# GC-Sch2.net
KiCad netlist of a schematic drawn in Altium Designer
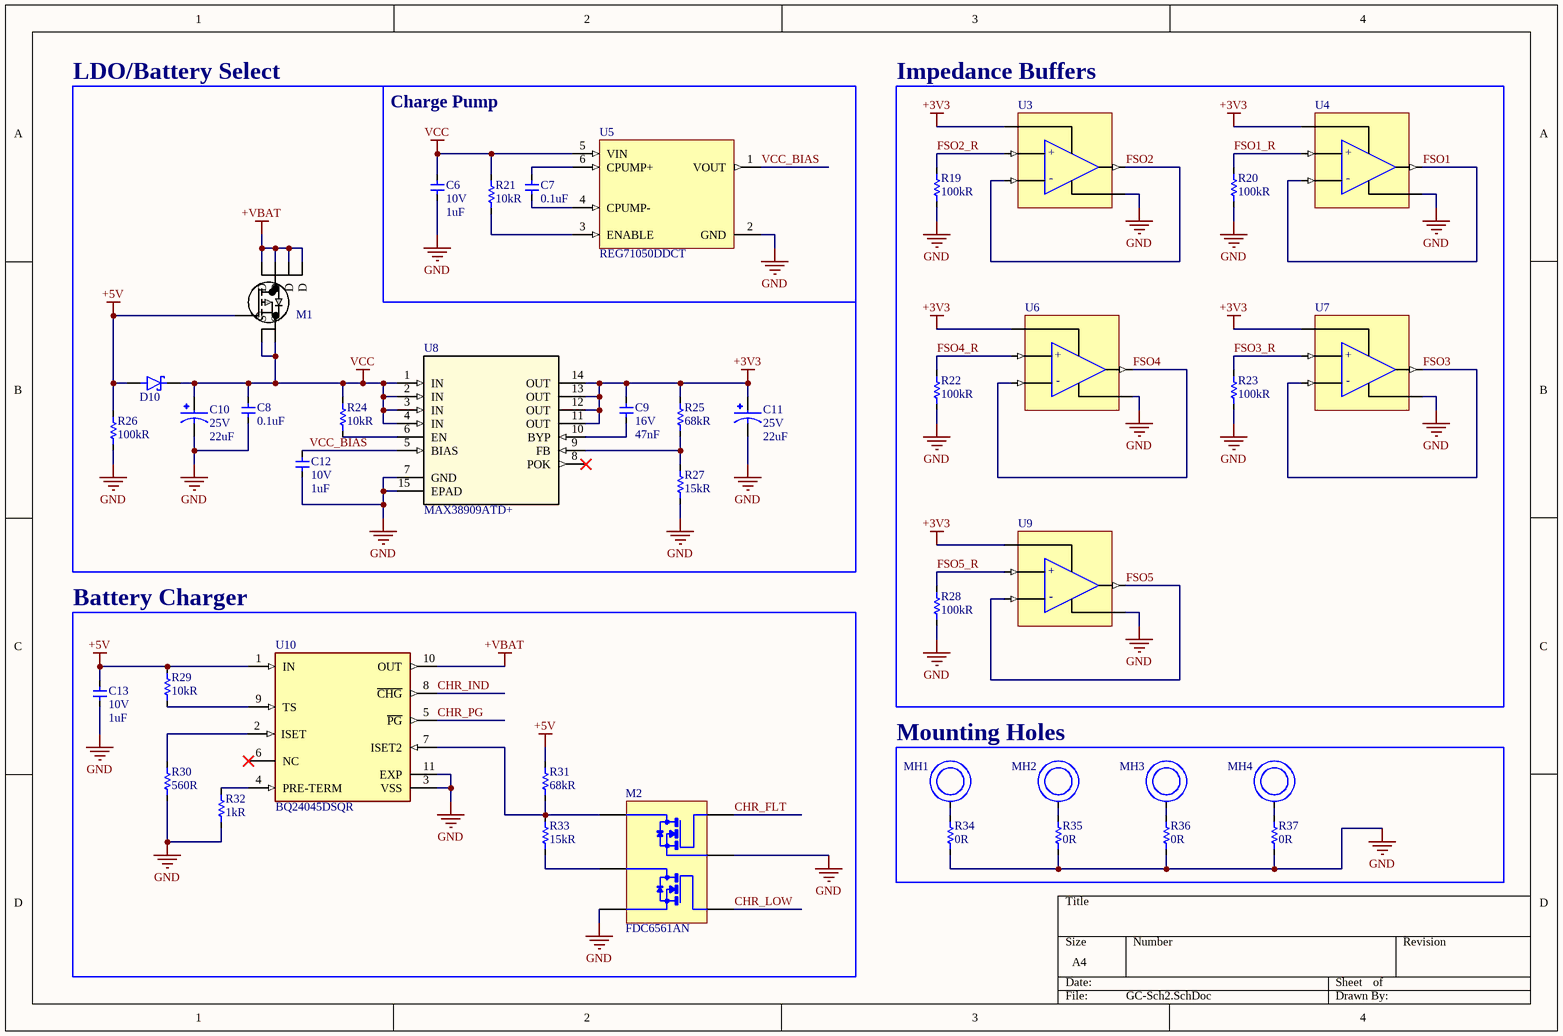
[diagram p0: GC-Sch2.SchDoc]

(export (version "E")
  (design (tool "Eeschema 10.0.6"))
  (components
    (comp (ref "C6")
      (value "CL10B105KP8NNNC")
      (footprint "0603 - C")
      (fields
        (field (name "MANUFACTURER") "Samsung")
        (field (name "RATED DC VOLTAGE (URDC)") "10V")
        (field (name "CAPACITANCE") "1uF")
      )
      (libsource (lib "GC-Schlib1") (part "CC-CL10B105KP8NNNC"))
    )
    (comp (ref "C7")
      (value "CL10B104JB8NNNC")
      (footprint "0603 - C")
      (fields (field (name "MANUFACTURER") "Samsung") (field (name "CAPACITANCE") "0.1uF"))
      (libsource (lib "GC-Schlib1") (part "CC-CL10B104JB8NNNC"))
    )
    (comp (ref "C8")
      (value "CL10B104JB8NNNC")
      (footprint "0603")
      (fields (field (name "MANUFACTURER") "Samsung") (field (name "CAPACITANCE") "0.1uF"))
      (libsource (lib "GC-Schlib1") (part "C-CL10B104JB8NNNC"))
    )
    (comp (ref "C9")
      (value "CL10B473KO8NNNC")
      (footprint "0603 - C")
      (fields
        (field (name "MANUFACTURER") "Samsung")
        (field (name "RATED DC VOLTAGE (URDC)") "16V")
        (field (name "CAPACITANCE") "47nF")
      )
      (libsource (lib "GC-Schlib1") (part "CC-CL10B473KO8NNNC"))
    )
    (comp (ref "C10")
      (value "EEE-FP1E220AR")
      (footprint "CC-25SVPF47M")
      (fields
        (field (name "MANUFACTURER") "Panasonic")
        (field (name "RATED DC VOLTAGE (URDC)") "25V")
        (field (name "CAPACITANCE") "22uF")
      )
      (libsource (lib "GC-Schlib1") (part "C-EEE-FP1E220AR"))
    )
    (comp (ref "C11")
      (value "EEE-FP1E220AR")
      (footprint "CC-25SVPF47M")
      (fields
        (field (name "MANUFACTURER") "Panasonic")
        (field (name "RATED DC VOLTAGE (URDC)") "25V")
        (field (name "CAPACITANCE") "22uF")
      )
      (libsource (lib "GC-Schlib1") (part "CC-EEE-FP1E220AR"))
    )
    (comp (ref "C12")
      (value "CL10B105KP8NNNC")
      (footprint "0603")
      (fields
        (field (name "MANUFACTURER") "Samsung")
        (field (name "RATED DC VOLTAGE (URDC)") "10V")
        (field (name "CAPACITANCE") "1uF")
      )
      (libsource (lib "GC-Schlib1") (part "C-CL10B105KP8NNNC"))
    )
    (comp (ref "C13")
      (value "CL10B105KP8NNNC")
      (footprint "0603 - C")
      (fields
        (field (name "MANUFACTURER") "Samsung")
        (field (name "RATED DC VOLTAGE (URDC)") "10V")
        (field (name "CAPACITANCE") "1uF")
      )
      (libsource (lib "GC-Schlib1") (part "CC-CL10B105KP8NNNC"))
    )
    (comp (ref "D10")
      (value "D-BAT760-7")
      (footprint "SOD2513X120N")
      (description "Rectifier Diode, Schottky, 1 Phase, 1 Element, 1A, 30V V(RRM), Silicon")
      (fields (field (name "MANUFACTURER") "Diodes") (field (name "MANUFACTURER PART NUMBER") "BAT760-7"))
      (libsource (lib "GC-Schlib1") (part "D-BAT760-7"))
    )
    (comp (ref "M1")
      (value "SIA427ADJ-T1-GE3")
      (footprint "SON_1DJ-T1-GE3_VIS")
      (fields (field (name "MANUFACTURER") "Vishay Siliconix"))
      (libsource (lib "GC-Schlib1") (part "M-SIA427ADJ-T1-GE3"))
    )
    (comp (ref "M2")
      (value "FDC6561AN")
      (footprint "SOT95P280X110-6N")
      (fields (field (name "MANUFACTURER") "ON Semiconductor / Fairchild"))
      (libsource (lib "GC-Schlib1") (part "M-FDC6561AN"))
    )
    (comp (ref "MH1")
      (value "M3 Screws")
      (footprint "M3 Screws")
      (libsource (lib "GC-Schlib1") (part "M3 Screws"))
    )
    (comp (ref "MH2")
      (value "M3 Screws")
      (footprint "M3 Screws")
      (libsource (lib "GC-Schlib1") (part "M3 Screws"))
    )
    (comp (ref "MH3")
      (value "M3 Screws")
      (footprint "M3 Screws")
      (libsource (lib "GC-Schlib1") (part "M3 Screws"))
    )
    (comp (ref "MH4")
      (value "M3 Screws")
      (footprint "M3 Screws")
      (libsource (lib "GC-Schlib1") (part "M3 Screws"))
    )
    (comp (ref "R19")
      (value "RC0603FR-07100KL")
      (footprint "0603 - R")
      (fields
        (field (name "MANUFACTURER") "Yageo")
        (field (name "TOLERANCE") "1%")
        (field (name "RESISTANCE") "100kR")
      )
      (libsource (lib "GC-Schlib1") (part "R-RC0603FR-07100KL"))
    )
    (comp (ref "R20")
      (value "RC0603FR-07100KL")
      (footprint "0603 - R")
      (fields
        (field (name "MANUFACTURER") "Yageo")
        (field (name "TOLERANCE") "1%")
        (field (name "RESISTANCE") "100kR")
      )
      (libsource (lib "GC-Schlib1") (part "R-RC0603FR-07100KL"))
    )
    (comp (ref "R21")
      (value "AC0603FR-1310KL")
      (footprint "0603 - R")
      (fields
        (field (name "MANUFACTURER") "Yageo")
        (field (name "TOLERANCE") "1%")
        (field (name "RESISTANCE") "10kR")
      )
      (libsource (lib "GC-Schlib1") (part "R-AC0603FR-1310KL"))
    )
    (comp (ref "R22")
      (value "RC0603FR-07100KL")
      (footprint "0603 - R")
      (fields
        (field (name "MANUFACTURER") "Yageo")
        (field (name "TOLERANCE") "1%")
        (field (name "RESISTANCE") "100kR")
      )
      (libsource (lib "GC-Schlib1") (part "R-RC0603FR-07100KL"))
    )
    (comp (ref "R23")
      (value "RC0603FR-07100KL")
      (footprint "0603 - R")
      (fields
        (field (name "MANUFACTURER") "Yageo")
        (field (name "TOLERANCE") "1%")
        (field (name "RESISTANCE") "100kR")
      )
      (libsource (lib "GC-Schlib1") (part "R-RC0603FR-07100KL"))
    )
    (comp (ref "R24")
      (value "AC0603FR-1310KL")
      (footprint "0603 - R")
      (fields
        (field (name "MANUFACTURER") "Yageo")
        (field (name "TOLERANCE") "1%")
        (field (name "RESISTANCE") "10kR")
      )
      (libsource (lib "GC-Schlib1") (part "R-AC0603FR-1310KL"))
    )
    (comp (ref "R25")
      (value "ERA-3AEB683V")
      (footprint "0603 - R")
      (description "Fixed Resistor, Thin Film, 0.1W, 68000ohm, 75V, 0.1% +/-Tol, 25ppm/Cel, Surface Mount, 0603")
      (fields
        (field (name "MANUFACTURER") "Panasonic")
        (field (name "TOLERANCE") "0.1%")
        (field (name "RESISTANCE") "68kR")
      )
      (libsource (lib "GC-Schlib1") (part "R-ERA-3AEB683V"))
    )
    (comp (ref "R26")
      (value "RC0603FR-07100KL")
      (footprint "0603 - R")
      (fields
        (field (name "MANUFACTURER") "Yageo")
        (field (name "TOLERANCE") "1%")
        (field (name "RESISTANCE") "100kR")
      )
      (libsource (lib "GC-Schlib1") (part "R-RC0603FR-07100KL"))
    )
    (comp (ref "R27")
      (value "ERA-3AEB153V")
      (footprint "0603 - R")
      (description "Fixed Resistor, Thin Film, 0.1W, 15000ohm, 75V, 0.1% +/-Tol, 25ppm/Cel, Surface Mount, 0603")
      (fields
        (field (name "MANUFACTURER") "Panasonic")
        (field (name "TOLERANCE") "0.1%")
        (field (name "RESISTANCE") "15kR")
      )
      (libsource (lib "GC-Schlib1") (part "R-ERA-3AEB153V"))
    )
    (comp (ref "R28")
      (value "RC0603FR-07100KL")
      (footprint "0603 - R")
      (fields
        (field (name "MANUFACTURER") "Yageo")
        (field (name "TOLERANCE") "1%")
        (field (name "RESISTANCE") "100kR")
      )
      (libsource (lib "GC-Schlib1") (part "R-RC0603FR-07100KL"))
    )
    (comp (ref "R29")
      (value "AC0603FR-1310KL")
      (footprint "0603 - R")
      (fields
        (field (name "MANUFACTURER") "Yageo")
        (field (name "TOLERANCE") "1%")
        (field (name "RESISTANCE") "10kR")
      )
      (libsource (lib "GC-Schlib1") (part "R-AC0603FR-1310KL"))
    )
    (comp (ref "R30")
      (value "ERJ-3EKF5600V")
      (footprint "0603 - R")
      (fields
        (field (name "MANUFACTURER") "Panasonic")
        (field (name "TOLERANCE") "1%")
        (field (name "RESISTANCE") "560R")
      )
      (libsource (lib "GC-Schlib1") (part "R-ERJ-3EKF5600V"))
    )
    (comp (ref "R31")
      (value "ERA-3AEB683V")
      (footprint "0603 - R")
      (description "Fixed Resistor, Thin Film, 0.1W, 68000ohm, 75V, 0.1% +/-Tol, 25ppm/Cel, Surface Mount, 0603")
      (fields
        (field (name "MANUFACTURER") "Panasonic")
        (field (name "TOLERANCE") "0.1%")
        (field (name "RESISTANCE") "68kR")
      )
      (libsource (lib "GC-Schlib1") (part "R-ERA-3AEB683V"))
    )
    (comp (ref "R32")
      (value "RC0603FR-071KL")
      (footprint "0603 - R")
      (fields
        (field (name "MANUFACTURER") "Yageo")
        (field (name "TOLERANCE") "1%")
        (field (name "RESISTANCE") "1kR")
      )
      (libsource (lib "GC-Schlib1") (part "R-RC0603FR-071KL"))
    )
    (comp (ref "R33")
      (value "ERA-3AEB153V")
      (footprint "0603 - R")
      (description "Fixed Resistor, Thin Film, 0.1W, 15000ohm, 75V, 0.1% +/-Tol, 25ppm/Cel, Surface Mount, 0603")
      (fields
        (field (name "MANUFACTURER") "Panasonic")
        (field (name "TOLERANCE") "0.1%")
        (field (name "RESISTANCE") "15kR")
      )
      (libsource (lib "GC-Schlib1") (part "R-ERA-3AEB153V"))
    )
    (comp (ref "R34")
      (value "ERJ-3GEY0R00V")
      (footprint "0603 - R")
      (description "Fixed Resistor, Metal Glaze/thick Film, 0.1W, 0ohm, Surface Mount, 0603")
      (fields (field (name "MANUFACTURER") "Panasonic") (field (name "RESISTANCE") "0R"))
      (libsource (lib "GC-Schlib1") (part "R-ERJ-3GEY0R00V"))
    )
    (comp (ref "R35")
      (value "ERJ-3GEY0R00V")
      (footprint "0603 - R")
      (description "Fixed Resistor, Metal Glaze/thick Film, 0.1W, 0ohm, Surface Mount, 0603")
      (fields (field (name "MANUFACTURER") "Panasonic") (field (name "RESISTANCE") "0R"))
      (libsource (lib "GC-Schlib1") (part "R-ERJ-3GEY0R00V"))
    )
    (comp (ref "R36")
      (value "ERJ-3GEY0R00V")
      (footprint "0603 - R")
      (description "Fixed Resistor, Metal Glaze/thick Film, 0.1W, 0ohm, Surface Mount, 0603")
      (fields (field (name "MANUFACTURER") "Panasonic") (field (name "RESISTANCE") "0R"))
      (libsource (lib "GC-Schlib1") (part "R-ERJ-3GEY0R00V"))
    )
    (comp (ref "R37")
      (value "ERJ-3GEY0R00V")
      (footprint "0603 - R")
      (description "Fixed Resistor, Metal Glaze/thick Film, 0.1W, 0ohm, Surface Mount, 0603")
      (fields (field (name "MANUFACTURER") "Panasonic") (field (name "RESISTANCE") "0R"))
      (libsource (lib "GC-Schlib1") (part "R-ERJ-3GEY0R00V"))
    )
    (comp (ref "U3")
      (value "MCP6071T-E/OT")
      (footprint "SOT95P270X145-5N")
      (description "Operational Amplifier, 1 Func, 150uV Offset-Max, CMOS, PDSO5")
      (fields (field (name "MANUFACTURER") "Microchip") (field (name "POWER") "No"))
      (libsource (lib "GC-Schlib1") (part "U-MCP6071T-E/OT"))
    )
    (comp (ref "U4")
      (value "MCP6071T-E/OT")
      (footprint "SOT95P270X145-5N")
      (description "Operational Amplifier, 1 Func, 150uV Offset-Max, CMOS, PDSO5")
      (fields (field (name "MANUFACTURER") "Microchip") (field (name "POWER") "No"))
      (libsource (lib "GC-Schlib1") (part "U-MCP6071T-E/OT"))
    )
    (comp (ref "U5")
      (value "REG71050DDCT")
      (footprint "SOT95P280X110-6N")
      (description "Switched Capacitor Converter, 0.06A, 1000kHz Switching Freq-Max, PDSO6")
      (fields (field (name "MANUFACTURER") "Texas Instruments"))
      (libsource (lib "GC-Schlib1") (part "U-REG71050DDC"))
    )
    (comp (ref "U6")
      (value "MCP6071T-E/OT")
      (footprint "SOT95P270X145-5N")
      (description "Operational Amplifier, 1 Func, 150uV Offset-Max, CMOS, PDSO5")
      (fields (field (name "MANUFACTURER") "Microchip") (field (name "POWER") "No"))
      (libsource (lib "GC-Schlib1") (part "U-MCP6071T-E/OT"))
    )
    (comp (ref "U7")
      (value "MCP6071T-E/OT")
      (footprint "SOT95P270X145-5N")
      (description "Operational Amplifier, 1 Func, 150uV Offset-Max, CMOS, PDSO5")
      (fields (field (name "MANUFACTURER") "Microchip") (field (name "POWER") "No"))
      (libsource (lib "GC-Schlib1") (part "U-MCP6071T-E/OT"))
    )
    (comp (ref "U8")
      (value "MAX38909ATD+")
      (footprint "21-0137I_T1433-2_MXM")
      (description "IC Reg Lin Pos Prog 4A 14TDFN")
      (fields (field (name "MANUFACTURER") "Analog Devices"))
      (libsource (lib "GC-Schlib1") (part "U-MAX38909ATD+"))
    )
    (comp (ref "U9")
      (value "MCP6071T-E/OT")
      (footprint "SOT95P270X145-5N")
      (description "Operational Amplifier, 1 Func, 150uV Offset-Max, CMOS, PDSO5")
      (fields (field (name "MANUFACTURER") "Microchip") (field (name "POWER") "No"))
      (libsource (lib "GC-Schlib1") (part "U-MCP6071T-E/OT"))
    )
    (comp (ref "U10")
      (value "BQ24045DSQR")
      (footprint "IC_BQ24045DSQR")
      (description "Power Supply Support Circuit, Adjustable, 1 Channel, 6.65, PDSO10")
      (fields (field (name "MANUFACTURER") "Texas Instruments"))
      (libsource (lib "GC-Schlib1") (part "U-BQ24045DSQR"))
    )
  )
  (nets
    (net (code "1") (name "+3V3") (class "Default")
      (node (ref "C11") (pin "1") (pinfunction "1_1") (pintype "passive"))
      (node (ref "C9") (pin "2") (pinfunction "2_2") (pintype "passive"))
      (node (ref "R25") (pin "2") (pinfunction "2_2") (pintype "passive"))
      (node (ref "U3") (pin "5") (pinfunction "VDD_5") (pintype "passive"))
      (node (ref "U4") (pin "5") (pinfunction "VDD_5") (pintype "passive"))
      (node (ref "U6") (pin "5") (pinfunction "VDD_5") (pintype "passive"))
      (node (ref "U7") (pin "5") (pinfunction "VDD_5") (pintype "passive"))
      (node (ref "U8") (pin "11") (pinfunction "OUT_11") (pintype "power_in"))
      (node (ref "U8") (pin "12") (pinfunction "OUT_12") (pintype "power_in"))
      (node (ref "U8") (pin "13") (pinfunction "OUT_13") (pintype "power_in"))
      (node (ref "U8") (pin "14") (pinfunction "OUT_14") (pintype "power_in"))
      (node (ref "U9") (pin "5") (pinfunction "VDD_5") (pintype "passive"))
    )
    (net (code "2") (name "+5V") (class "Default")
      (node (ref "C13") (pin "2") (pinfunction "2_2") (pintype "passive"))
      (node (ref "D10") (pin "A") (pinfunction "A_A") (pintype "passive"))
      (node (ref "M1") (pin "3") (pinfunction "G_3") (pintype "passive"))
      (node (ref "R26") (pin "2") (pinfunction "2_2") (pintype "passive"))
      (node (ref "R29") (pin "2") (pinfunction "2_2") (pintype "passive"))
      (node (ref "R31") (pin "2") (pinfunction "2_2") (pintype "passive"))
      (node (ref "U10") (pin "1") (pinfunction "IN_1") (pintype "input"))
    )
    (net (code "3") (name "+VBAT") (class "Default")
      (node (ref "M1") (pin "1") (pinfunction "D_1") (pintype "passive"))
      (node (ref "M1") (pin "2") (pinfunction "D_2") (pintype "passive"))
      (node (ref "M1") (pin "5") (pinfunction "D_5") (pintype "passive"))
      (node (ref "M1") (pin "6") (pinfunction "D_6") (pintype "passive"))
      (node (ref "U10") (pin "10") (pinfunction "OUT_10") (pintype "output"))
    )
    (net (code "4") (name "/CHR_FLT") (class "Default")
      (node (ref "M2") (pin "3") (pinfunction "G2_3") (pintype "passive"))
    )
    (net (code "5") (name "/CHR_IND") (class "Default")
      (node (ref "U10") (pin "8") (pinfunction "~{CHG}_8") (pintype "output"))
    )
    (net (code "6") (name "/CHR_LOW") (class "Default")
      (node (ref "M2") (pin "1") (pinfunction "G1_1") (pintype "passive"))
    )
    (net (code "7") (name "/CHR_PG") (class "Default")
      (node (ref "U10") (pin "5") (pinfunction "~{PG}_5") (pintype "output"))
    )
    (net (code "8") (name "/FSO1") (class "Default")
      (node (ref "U4") (pin "1") (pinfunction "VOUT_1") (pintype "output"))
      (node (ref "U4") (pin "4") (pinfunction "VIN-_4") (pintype "input"))
    )
    (net (code "9") (name "/FSO1_R") (class "Default")
      (node (ref "R20") (pin "2") (pinfunction "2_2") (pintype "passive"))
      (node (ref "U4") (pin "3") (pinfunction "VIN+_3") (pintype "input"))
    )
    (net (code "10") (name "/FSO2") (class "Default")
      (node (ref "U3") (pin "1") (pinfunction "VOUT_1") (pintype "output"))
      (node (ref "U3") (pin "4") (pinfunction "VIN-_4") (pintype "input"))
    )
    (net (code "11") (name "/FSO2_R") (class "Default")
      (node (ref "R19") (pin "2") (pinfunction "2_2") (pintype "passive"))
      (node (ref "U3") (pin "3") (pinfunction "VIN+_3") (pintype "input"))
    )
    (net (code "12") (name "/FSO3") (class "Default")
      (node (ref "U7") (pin "1") (pinfunction "VOUT_1") (pintype "output"))
      (node (ref "U7") (pin "4") (pinfunction "VIN-_4") (pintype "input"))
    )
    (net (code "13") (name "/FSO3_R") (class "Default")
      (node (ref "R23") (pin "2") (pinfunction "2_2") (pintype "passive"))
      (node (ref "U7") (pin "3") (pinfunction "VIN+_3") (pintype "input"))
    )
    (net (code "14") (name "/FSO4") (class "Default")
      (node (ref "U6") (pin "1") (pinfunction "VOUT_1") (pintype "output"))
      (node (ref "U6") (pin "4") (pinfunction "VIN-_4") (pintype "input"))
    )
    (net (code "15") (name "/FSO4_R") (class "Default")
      (node (ref "R22") (pin "2") (pinfunction "2_2") (pintype "passive"))
      (node (ref "U6") (pin "3") (pinfunction "VIN+_3") (pintype "input"))
    )
    (net (code "16") (name "/FSO5") (class "Default")
      (node (ref "U9") (pin "1") (pinfunction "VOUT_1") (pintype "output"))
      (node (ref "U9") (pin "4") (pinfunction "VIN-_4") (pintype "input"))
    )
    (net (code "17") (name "/FSO5_R") (class "Default")
      (node (ref "R28") (pin "2") (pinfunction "2_2") (pintype "passive"))
      (node (ref "U9") (pin "3") (pinfunction "VIN+_3") (pintype "input"))
    )
    (net (code "18") (name "/VCC_BIAS") (class "Default")
      (node (ref "C12") (pin "2") (pinfunction "2_2") (pintype "passive"))
      (node (ref "U5") (pin "1") (pinfunction "VOUT_1") (pintype "output"))
      (node (ref "U8") (pin "5") (pinfunction "BIAS_5") (pintype "input"))
    )
    (net (code "19") (name "GND") (class "Default")
      (node (ref "C10") (pin "2") (pinfunction "2_2") (pintype "passive"))
      (node (ref "C11") (pin "2") (pinfunction "2_2") (pintype "passive"))
      (node (ref "C12") (pin "1") (pinfunction "1_1") (pintype "passive"))
      (node (ref "C13") (pin "1") (pinfunction "1_1") (pintype "passive"))
      (node (ref "C6") (pin "1") (pinfunction "1_1") (pintype "passive"))
      (node (ref "C8") (pin "1") (pinfunction "1_1") (pintype "passive"))
      (node (ref "M2") (pin "2") (pinfunction "S2_2") (pintype "passive"))
      (node (ref "M2") (pin "5") (pinfunction "S1_5") (pintype "passive"))
      (node (ref "R19") (pin "1") (pinfunction "1_1") (pintype "passive"))
      (node (ref "R20") (pin "1") (pinfunction "1_1") (pintype "passive"))
      (node (ref "R22") (pin "1") (pinfunction "1_1") (pintype "passive"))
      (node (ref "R23") (pin "1") (pinfunction "1_1") (pintype "passive"))
      (node (ref "R26") (pin "1") (pinfunction "1_1") (pintype "passive"))
      (node (ref "R27") (pin "1") (pinfunction "1_1") (pintype "passive"))
      (node (ref "R28") (pin "1") (pinfunction "1_1") (pintype "passive"))
      (node (ref "R30") (pin "1") (pinfunction "1_1") (pintype "passive"))
      (node (ref "R32") (pin "1") (pinfunction "1_1") (pintype "passive"))
      (node (ref "R34") (pin "1") (pinfunction "1_1") (pintype "passive"))
      (node (ref "R35") (pin "1") (pinfunction "1_1") (pintype "passive"))
      (node (ref "R36") (pin "1") (pinfunction "1_1") (pintype "passive"))
      (node (ref "R37") (pin "1") (pinfunction "1_1") (pintype "passive"))
      (node (ref "U10") (pin "11") (pinfunction "EXP_11") (pintype "power_in"))
      (node (ref "U10") (pin "3") (pinfunction "VSS_3") (pintype "power_in"))
      (node (ref "U3") (pin "2") (pinfunction "VSS_2") (pintype "passive"))
      (node (ref "U4") (pin "2") (pinfunction "VSS_2") (pintype "passive"))
      (node (ref "U5") (pin "2") (pinfunction "GND_2") (pintype "power_in"))
      (node (ref "U6") (pin "2") (pinfunction "VSS_2") (pintype "passive"))
      (node (ref "U7") (pin "2") (pinfunction "VSS_2") (pintype "passive"))
      (node (ref "U8") (pin "15") (pinfunction "EPAD_15") (pintype "power_in"))
      (node (ref "U8") (pin "7") (pinfunction "GND_7") (pintype "power_in"))
      (node (ref "U9") (pin "2") (pinfunction "VSS_2") (pintype "passive"))
    )
    (net (code "20") (name "Net-(M2-D1)") (class "Default")
      (node (ref "M2") (pin "6") (pinfunction "D1_6") (pintype "passive"))
      (node (ref "R33") (pin "1") (pinfunction "1_1") (pintype "passive"))
    )
    (net (code "21") (name "Net-(M2-D2)") (class "Default")
      (node (ref "M2") (pin "4") (pinfunction "D2_4") (pintype "passive"))
      (node (ref "R31") (pin "1") (pinfunction "1_1") (pintype "passive"))
      (node (ref "R33") (pin "2") (pinfunction "2_2") (pintype "passive"))
      (node (ref "U10") (pin "7") (pinfunction "ISET2_7") (pintype "input"))
    )
    (net (code "22") (name "Net-(MH1-Pad1)") (class "Default")
      (node (ref "MH1") (pin "1") (pintype "passive"))
      (node (ref "R34") (pin "2") (pinfunction "2_2") (pintype "passive"))
    )
    (net (code "23") (name "Net-(MH2-Pad1)") (class "Default")
      (node (ref "MH2") (pin "1") (pintype "passive"))
      (node (ref "R35") (pin "2") (pinfunction "2_2") (pintype "passive"))
    )
    (net (code "24") (name "Net-(MH3-Pad1)") (class "Default")
      (node (ref "MH3") (pin "1") (pintype "passive"))
      (node (ref "R36") (pin "2") (pinfunction "2_2") (pintype "passive"))
    )
    (net (code "25") (name "Net-(MH4-Pad1)") (class "Default")
      (node (ref "MH4") (pin "1") (pintype "passive"))
      (node (ref "R37") (pin "2") (pinfunction "2_2") (pintype "passive"))
    )
    (net (code "26") (name "Net-(U5-CPUMP+)") (class "Default")
      (node (ref "C7") (pin "2") (pinfunction "2_2") (pintype "passive"))
      (node (ref "U5") (pin "6") (pinfunction "CPUMP+_6") (pintype "input"))
    )
    (net (code "27") (name "Net-(U5-CPUMP-)") (class "Default")
      (node (ref "C7") (pin "1") (pinfunction "1_1") (pintype "passive"))
      (node (ref "U5") (pin "4") (pinfunction "CPUMP-_4") (pintype "input"))
    )
    (net (code "28") (name "Net-(U5-ENABLE)") (class "Default")
      (node (ref "R21") (pin "1") (pinfunction "1_1") (pintype "passive"))
      (node (ref "U5") (pin "3") (pinfunction "ENABLE_3") (pintype "input"))
    )
    (net (code "29") (name "Net-(U8-BYP)") (class "Default")
      (node (ref "C9") (pin "1") (pinfunction "1_1") (pintype "passive"))
      (node (ref "U8") (pin "10") (pinfunction "BYP_10") (pintype "input"))
    )
    (net (code "30") (name "Net-(U8-EN)") (class "Default")
      (node (ref "R24") (pin "1") (pinfunction "1_1") (pintype "passive"))
      (node (ref "U8") (pin "6") (pinfunction "EN_6") (pintype "passive"))
    )
    (net (code "31") (name "Net-(U8-FB)") (class "Default")
      (node (ref "R25") (pin "1") (pinfunction "1_1") (pintype "passive"))
      (node (ref "R27") (pin "2") (pinfunction "2_2") (pintype "passive"))
      (node (ref "U8") (pin "9") (pinfunction "FB_9") (pintype "input"))
    )
    (net (code "32") (name "Net-(U10-ISET)") (class "Default")
      (node (ref "R30") (pin "2") (pinfunction "2_2") (pintype "passive"))
      (node (ref "U10") (pin "2") (pinfunction "ISET_2") (pintype "input"))
    )
    (net (code "33") (name "Net-(U10-PRE-TERM)") (class "Default")
      (node (ref "R32") (pin "2") (pinfunction "2_2") (pintype "passive"))
      (node (ref "U10") (pin "4") (pinfunction "PRE-TERM_4") (pintype "input"))
    )
    (net (code "34") (name "Net-(U10-TS)") (class "Default")
      (node (ref "R29") (pin "1") (pinfunction "1_1") (pintype "passive"))
      (node (ref "U10") (pin "9") (pinfunction "TS_9") (pintype "input"))
    )
    (net (code "35") (name "VCC") (class "Default")
      (node (ref "C10") (pin "1") (pinfunction "1_1") (pintype "passive"))
      (node (ref "C6") (pin "2") (pinfunction "2_2") (pintype "passive"))
      (node (ref "C8") (pin "2") (pinfunction "2_2") (pintype "passive"))
      (node (ref "D10") (pin "C") (pinfunction "K_C") (pintype "passive"))
      (node (ref "M1") (pin "4") (pinfunction "S_4") (pintype "passive"))
      (node (ref "M1") (pin "7") (pinfunction "S_7") (pintype "passive"))
      (node (ref "R21") (pin "2") (pinfunction "2_2") (pintype "passive"))
      (node (ref "R24") (pin "2") (pinfunction "2_2") (pintype "passive"))
      (node (ref "U5") (pin "5") (pinfunction "VIN_5") (pintype "input"))
      (node (ref "U8") (pin "1") (pinfunction "IN_1") (pintype "input"))
      (node (ref "U8") (pin "2") (pinfunction "IN_2") (pintype "input"))
      (node (ref "U8") (pin "3") (pinfunction "IN_3") (pintype "input"))
      (node (ref "U8") (pin "4") (pinfunction "IN_4") (pintype "input"))
    )
    (net (code "36") (name "unconnected-(U8-POK-Pad8)") (class "Default")
      (node (ref "U8") (pin "8") (pinfunction "POK_8") (pintype "output+no_connect"))
    )
    (net (code "37") (name "unconnected-(U10-NC-Pad6)") (class "Default")
      (node (ref "U10") (pin "6") (pinfunction "NC_6") (pintype "passive+no_connect"))
    )
  )
)
